# cd_switching.net
KiCad netlist of a schematic drawn in Altium Designer
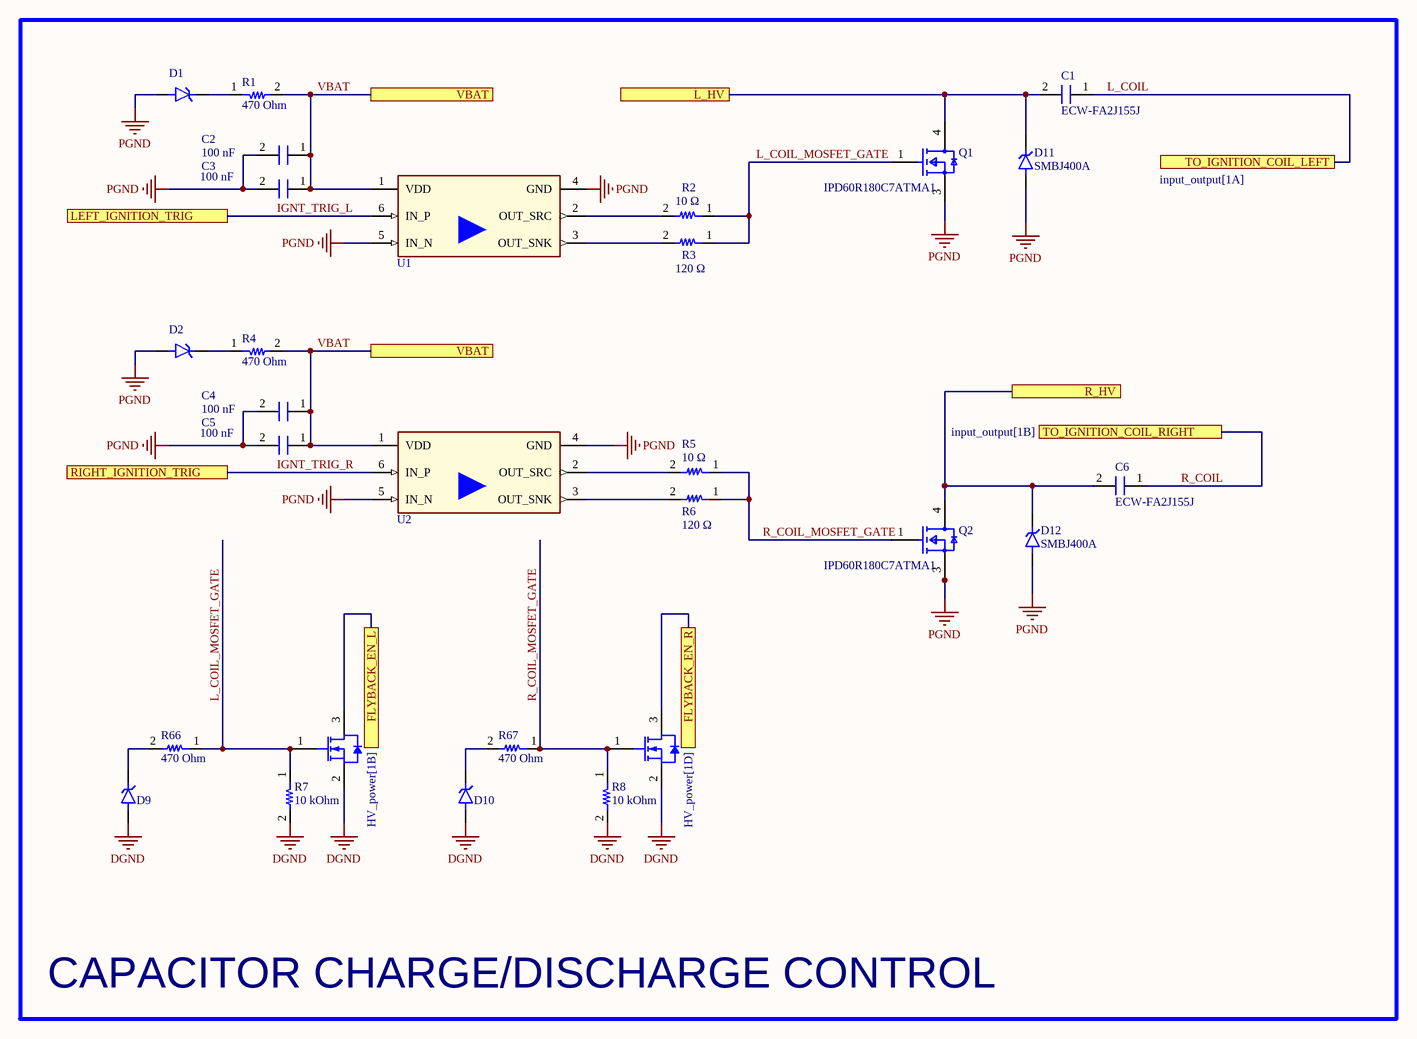
[diagram p0: cd_switching.SchDoc]

(export (version "E")
  (design (tool "Eeschema 10.0.6"))
  (components
    (comp (ref "C1")
      (value "ECW-FA2J155J")
      (footprint "22,5mm_CAP")
      (libsource (lib "RC_sch") (part "Capacitor_THT_22.5mm"))
    )
    (comp (ref "C2")
      (value "100 nF")
      (footprint "0603_FP")
      (fields (field (name "Comment") "Capacitor_0603"))
      (libsource (lib "RC_sch") (part "Capacitor_0603"))
    )
    (comp (ref "C3")
      (value "100 nF")
      (footprint "0603_FP")
      (fields (field (name "Comment") "Capacitor_0603"))
      (libsource (lib "RC_sch") (part "Capacitor_0603"))
    )
    (comp (ref "C4")
      (value "100 nF")
      (footprint "0603_FP")
      (fields (field (name "Comment") "Capacitor_0603"))
      (libsource (lib "RC_sch") (part "Capacitor_0603"))
    )
    (comp (ref "C5")
      (value "100 nF")
      (footprint "0603_FP")
      (fields (field (name "Comment") "Capacitor_0603"))
      (libsource (lib "RC_sch") (part "Capacitor_0603"))
    )
    (comp (ref "C6")
      (value "ECW-FA2J155J")
      (footprint "22,5mm_CAP")
      (libsource (lib "RC_sch") (part "Capacitor_THT_22.5mm"))
    )
    (comp (ref "D1")
      (value "BZT52B15SH_RRG")
      (footprint "DIO_BZT52B15SH_RRG")
      (description "SOD-323, 200mW, 2%, 15V, Zener Diode")
      (fields (field (name "MF") "Taiwan Semiconductor Corporation") (field (name "MP") "BZT52B15SH RRG"))
      (libsource (lib "BZT52B15SH_RRG") (part "BZT52B15SH_RRG"))
    )
    (comp (ref "D2")
      (value "BZT52B15SH_RRG")
      (footprint "DIO_BZT52B15SH_RRG")
      (description "SOD-323, 200mW, 2%, 15V, Zener Diode")
      (fields (field (name "MF") "Taiwan Semiconductor Corporation") (field (name "MP") "BZT52B15SH RRG"))
      (libsource (lib "BZT52B15SH_RRG") (part "BZT52B15SH_RRG"))
    )
    (comp (ref "D9")
      (value "BZT52B15SH_RRG")
      (footprint "DIO_BZT52B15SH_RRG")
      (description "SOD-323, 200mW, 2%, 15V, Zener Diode")
      (fields (field (name "MF") "Taiwan Semiconductor Corporation") (field (name "MP") "BZT52B15SH RRG"))
      (libsource (lib "BZT52B15SH_RRG") (part "BZT52B15SH_RRG"))
    )
    (comp (ref "D10")
      (value "BZT52B15SH_RRG")
      (footprint "DIO_BZT52B15SH_RRG")
      (description "SOD-323, 200mW, 2%, 15V, Zener Diode")
      (fields (field (name "MF") "Taiwan Semiconductor Corporation") (field (name "MP") "BZT52B15SH RRG"))
      (libsource (lib "BZT52B15SH_RRG") (part "BZT52B15SH_RRG"))
    )
    (comp (ref "D11")
      (value "SMBJ400A")
      (footprint "DIOM5436X261N")
      (description "Pince 648V 900mA Ipp TVS Diode Surface Mount DO-214AA (SMBJ)")
      (fields (field (name "MF") "Littelfuse"))
      (libsource (lib "SMBJ400A") (part "SMBJ400A"))
    )
    (comp (ref "D12")
      (value "SMBJ400A")
      (footprint "DIOM5436X261N")
      (description "Pince 648V 900mA Ipp TVS Diode Surface Mount DO-214AA (SMBJ)")
      (fields (field (name "MF") "Littelfuse"))
      (libsource (lib "SMBJ400A") (part "SMBJ400A"))
    )
    (comp (ref "Q1")
      (value "IPD60R180C7ATMA1")
      (footprint "FP-PG-TO252-3-MFG")
      (description "IPD60R180C7ATMA1 Trans MOSFET N-CH 600V 13A 3-Pin(2+Tab) DPAK T/R")
      (libsource (lib "Altium Content Vault") (part "2d7d0ff8398697ccf209b23a854e578"))
    )
    (comp (ref "Q2")
      (value "IPD60R180C7ATMA1")
      (footprint "FP-PG-TO252-3-MFG")
      (description "IPD60R180C7ATMA1 Trans MOSFET N-CH 600V 13A 3-Pin(2+Tab) DPAK T/R")
      (libsource (lib "Altium Content Vault") (part "2d7d0ff8398697ccf209b23a854e578"))
    )
    (comp (ref "Q3")
      (value "MGSF1N03LT1G")
      (footprint "ONSC-SOT-23-3-318-08_V")
      (description "Power MOSFET, 30 V, 2.1 A, Single N-Channel, 3-Pin SOT-23, Pb-Free, Tape and Reel")
      (fields (field (name "MANUFACTURER") "On Semiconductor"))
      (libsource (lib "Altium Content Vault") (part "ONSC-NMOS-G1S2D3-3"))
    )
    (comp (ref "Q4")
      (value "MGSF1N03LT1G")
      (footprint "ONSC-SOT-23-3-318-08_V")
      (description "Power MOSFET, 30 V, 2.1 A, Single N-Channel, 3-Pin SOT-23, Pb-Free, Tape and Reel")
      (fields (field (name "MANUFACTURER") "On Semiconductor"))
      (libsource (lib "Altium Content Vault") (part "ONSC-NMOS-G1S2D3-3"))
    )
    (comp (ref "R1")
      (value "470 Ohm")
      (footprint "0603_FP")
      (fields (field (name "Comment") "Resistor_0603"))
      (libsource (lib "RC_sch") (part "Resistor_0603"))
    )
    (comp (ref "R2")
      (value "10 Ω")
      (footprint "0603_FP")
      (fields (field (name "Comment") "Resistor_0603"))
      (libsource (lib "RC_sch") (part "Resistor_0603"))
    )
    (comp (ref "R3")
      (value "120 Ω")
      (footprint "0603_FP")
      (fields (field (name "Comment") "Resistor_0603"))
      (libsource (lib "RC_sch") (part "Resistor_0603"))
    )
    (comp (ref "R4")
      (value "470 Ohm")
      (footprint "0603_FP")
      (fields (field (name "Comment") "Resistor_0603"))
      (libsource (lib "RC_sch") (part "Resistor_0603"))
    )
    (comp (ref "R5")
      (value "10 Ω")
      (footprint "0603_FP")
      (fields (field (name "Comment") "Resistor_0603"))
      (libsource (lib "RC_sch") (part "Resistor_0603"))
    )
    (comp (ref "R6")
      (value "120 Ω")
      (footprint "0603_FP")
      (fields (field (name "Comment") "Resistor_0603"))
      (libsource (lib "RC_sch") (part "Resistor_0603"))
    )
    (comp (ref "R7")
      (value "10 kOhm")
      (footprint "0402_fp")
      (fields (field (name "Comment") "Resistor_0402"))
      (libsource (lib "RC_sch") (part "Resistor_0402"))
    )
    (comp (ref "R8")
      (value "10 kOhm")
      (footprint "0402_fp")
      (fields (field (name "Comment") "Resistor_0402"))
      (libsource (lib "RC_sch") (part "Resistor_0402"))
    )
    (comp (ref "R66")
      (value "470 Ohm")
      (footprint "0603_FP")
      (fields (field (name "Comment") "Resistor_0603"))
      (libsource (lib "RC_sch") (part "Resistor_0603"))
    )
    (comp (ref "R67")
      (value "470 Ohm")
      (footprint "0603_FP")
      (fields (field (name "Comment") "Resistor_0603"))
      (libsource (lib "RC_sch") (part "Resistor_0603"))
    )
    (comp (ref "U1")
      (value "1EDN7511B")
      (footprint "SOT95P280X145-6N-7-V")
      (description "EiceDRIVER, Fast Single Channel 4A/8A Low-Side Gate Driver, UVLO - 4.2V")
      (fields (field (name "MANUFACTURER") "Infineon Technologies"))
      (libsource (lib "1EDN7511B") (part "1EDN7511B"))
    )
    (comp (ref "U2")
      (value "1EDN7511B")
      (footprint "SOT95P280X145-6N-7-V")
      (description "EiceDRIVER, Fast Single Channel 4A/8A Low-Side Gate Driver, UVLO - 4.2V")
      (fields (field (name "MANUFACTURER") "Infineon Technologies"))
      (libsource (lib "1EDN7511B") (part "1EDN7511B"))
    )
  )
  (nets
    (net (code "1") (name "/FLYBACK_EN_L") (class "Default")
      (node (ref "Q3") (pin "3") (pinfunction "D_3") (pintype "passive"))
    )
    (net (code "2") (name "/FLYBACK_EN_R") (class "Default")
      (node (ref "Q4") (pin "3") (pinfunction "D_3") (pintype "passive"))
    )
    (net (code "3") (name "/IGNT_TRIG_L") (class "Default")
      (node (ref "U1") (pin "6") (pinfunction "IN_P_6") (pintype "input"))
    )
    (net (code "4") (name "/IGNT_TRIG_R") (class "Default")
      (node (ref "U2") (pin "6") (pinfunction "IN_P_6") (pintype "input"))
    )
    (net (code "5") (name "/L_COIL") (class "Default")
      (node (ref "C1") (pin "1") (pinfunction "1_1") (pintype "passive"))
    )
    (net (code "6") (name "/L_COIL_MOSFET_GATE") (class "Default")
      (node (ref "Q1") (pin "1") (pinfunction "Gate_1") (pintype "passive"))
      (node (ref "Q3") (pin "1") (pinfunction "G_1") (pintype "passive"))
      (node (ref "R2") (pin "1") (pinfunction "1_1") (pintype "passive"))
      (node (ref "R3") (pin "1") (pinfunction "1_1") (pintype "passive"))
      (node (ref "R66") (pin "1") (pinfunction "1_1") (pintype "passive"))
      (node (ref "R7") (pin "1") (pinfunction "1_1") (pintype "passive"))
    )
    (net (code "7") (name "/L_HV") (class "Default")
      (node (ref "C1") (pin "2") (pinfunction "2_2") (pintype "passive"))
      (node (ref "D11") (pin "1") (pinfunction "K_1") (pintype "passive"))
      (node (ref "Q1") (pin "4") (pinfunction "Drain_4") (pintype "passive"))
    )
    (net (code "8") (name "/R_COIL") (class "Default")
      (node (ref "C6") (pin "1") (pinfunction "1_1") (pintype "passive"))
    )
    (net (code "9") (name "/R_COIL_MOSFET_GATE") (class "Default")
      (node (ref "Q2") (pin "1") (pinfunction "Gate_1") (pintype "passive"))
      (node (ref "Q4") (pin "1") (pinfunction "G_1") (pintype "passive"))
      (node (ref "R5") (pin "1") (pinfunction "1_1") (pintype "passive"))
      (node (ref "R6") (pin "1") (pinfunction "1_1") (pintype "passive"))
      (node (ref "R67") (pin "1") (pinfunction "1_1") (pintype "passive"))
      (node (ref "R8") (pin "1") (pinfunction "1_1") (pintype "passive"))
    )
    (net (code "10") (name "/R_HV") (class "Default")
      (node (ref "C6") (pin "2") (pinfunction "2_2") (pintype "passive"))
      (node (ref "D12") (pin "1") (pinfunction "K_1") (pintype "passive"))
      (node (ref "Q2") (pin "4") (pinfunction "Drain_4") (pintype "passive"))
    )
    (net (code "11") (name "/VBAT") (class "Default")
      (node (ref "C2") (pin "1") (pinfunction "1_1") (pintype "passive"))
      (node (ref "C3") (pin "1") (pinfunction "1_1") (pintype "passive"))
      (node (ref "C4") (pin "1") (pinfunction "1_1") (pintype "passive"))
      (node (ref "C5") (pin "1") (pinfunction "1_1") (pintype "passive"))
      (node (ref "R1") (pin "2") (pinfunction "2_2") (pintype "passive"))
      (node (ref "R4") (pin "2") (pinfunction "2_2") (pintype "passive"))
      (node (ref "U1") (pin "1") (pinfunction "VDD_1") (pintype "power_in"))
      (node (ref "U2") (pin "1") (pinfunction "VDD_1") (pintype "power_in"))
    )
    (net (code "12") (name "DGND") (class "Default")
      (node (ref "D10") (pin "2") (pinfunction "A_2") (pintype "passive"))
      (node (ref "D9") (pin "2") (pinfunction "A_2") (pintype "passive"))
      (node (ref "Q3") (pin "2") (pinfunction "S_2") (pintype "passive"))
      (node (ref "Q4") (pin "2") (pinfunction "S_2") (pintype "passive"))
      (node (ref "R7") (pin "2") (pinfunction "2_2") (pintype "passive"))
      (node (ref "R8") (pin "2") (pinfunction "2_2") (pintype "passive"))
    )
    (net (code "13") (name "Net-(D1-K)") (class "Default")
      (node (ref "D1") (pin "1") (pinfunction "K_1") (pintype "passive"))
      (node (ref "R1") (pin "1") (pinfunction "1_1") (pintype "passive"))
    )
    (net (code "14") (name "Net-(D2-K)") (class "Default")
      (node (ref "D2") (pin "1") (pinfunction "K_1") (pintype "passive"))
      (node (ref "R4") (pin "1") (pinfunction "1_1") (pintype "passive"))
    )
    (net (code "15") (name "Net-(D9-K)") (class "Default")
      (node (ref "D9") (pin "1") (pinfunction "K_1") (pintype "passive"))
      (node (ref "R66") (pin "2") (pinfunction "2_2") (pintype "passive"))
    )
    (net (code "16") (name "Net-(D10-K)") (class "Default")
      (node (ref "D10") (pin "1") (pinfunction "K_1") (pintype "passive"))
      (node (ref "R67") (pin "2") (pinfunction "2_2") (pintype "passive"))
    )
    (net (code "17") (name "Net-(U1-OUT_SNK)") (class "Default")
      (node (ref "R3") (pin "2") (pinfunction "2_2") (pintype "passive"))
      (node (ref "U1") (pin "3") (pinfunction "OUT_SNK_3") (pintype "output"))
    )
    (net (code "18") (name "Net-(U1-OUT_SRC)") (class "Default")
      (node (ref "R2") (pin "2") (pinfunction "2_2") (pintype "passive"))
      (node (ref "U1") (pin "2") (pinfunction "OUT_SRC_2") (pintype "output"))
    )
    (net (code "19") (name "Net-(U2-OUT_SNK)") (class "Default")
      (node (ref "R6") (pin "2") (pinfunction "2_2") (pintype "passive"))
      (node (ref "U2") (pin "3") (pinfunction "OUT_SNK_3") (pintype "output"))
    )
    (net (code "20") (name "Net-(U2-OUT_SRC)") (class "Default")
      (node (ref "R5") (pin "2") (pinfunction "2_2") (pintype "passive"))
      (node (ref "U2") (pin "2") (pinfunction "OUT_SRC_2") (pintype "output"))
    )
    (net (code "21") (name "PGND") (class "Default")
      (node (ref "C2") (pin "2") (pinfunction "2_2") (pintype "passive"))
      (node (ref "C3") (pin "2") (pinfunction "2_2") (pintype "passive"))
      (node (ref "C4") (pin "2") (pinfunction "2_2") (pintype "passive"))
      (node (ref "C5") (pin "2") (pinfunction "2_2") (pintype "passive"))
      (node (ref "D1") (pin "2") (pinfunction "A_2") (pintype "passive"))
      (node (ref "D11") (pin "2") (pinfunction "A_2") (pintype "passive"))
      (node (ref "D12") (pin "2") (pinfunction "A_2") (pintype "passive"))
      (node (ref "D2") (pin "2") (pinfunction "A_2") (pintype "passive"))
      (node (ref "Q1") (pin "3") (pinfunction "Source_3") (pintype "passive"))
      (node (ref "Q2") (pin "3") (pinfunction "Source_3") (pintype "passive"))
      (node (ref "U1") (pin "4") (pinfunction "GND_4") (pintype "power_in"))
      (node (ref "U1") (pin "5") (pinfunction "IN_N_5") (pintype "input"))
      (node (ref "U2") (pin "4") (pinfunction "GND_4") (pintype "power_in"))
      (node (ref "U2") (pin "5") (pinfunction "IN_N_5") (pintype "input"))
    )
  )
)
